# Rev2_7500-8500.net
KiCad netlist of a schematic drawn in Altium Designer
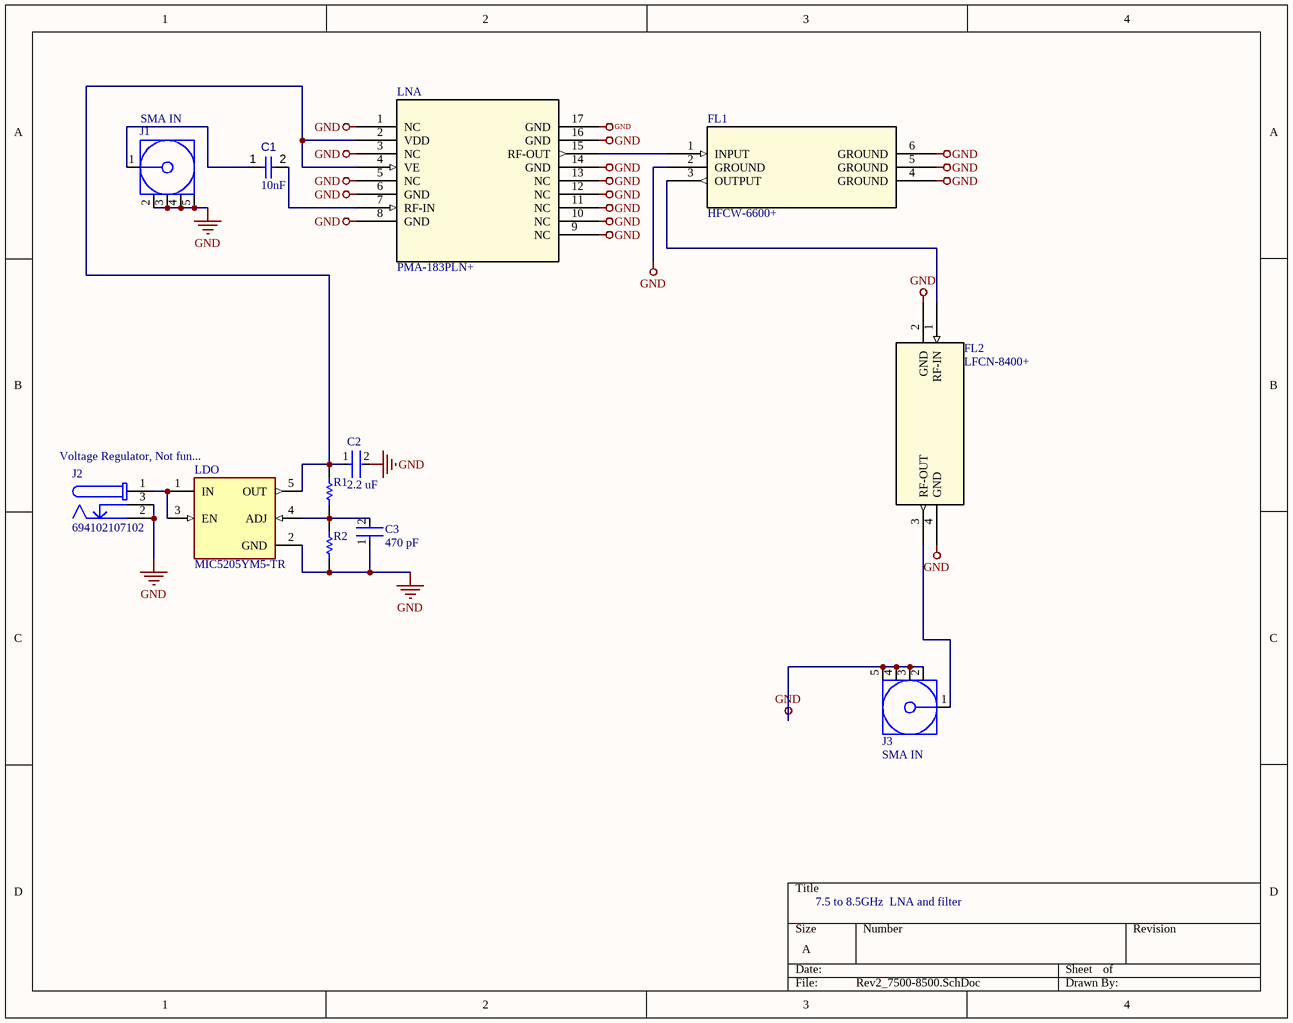
[diagram p0: Rev2_7500-8500.SchDoc]

(export (version "E")
  (design (tool "Eeschema 10.0.6"))
  (components
    (comp (ref "C1")
      (value "10nF")
      (footprint "CAPC0402(1005)60_L")
      (description "Chip Capacitor, 10nF +/-20%, 50V, 0402, Thickness 0.6 mm")
      (fields (field (name "TOLERANCE") "5%") (field (name "Comment") "Capacitor 10nF +/-20% 50V 0402"))
      (libsource (lib "X-Band Circuit") (part "CAP-NP-2"))
    )
    (comp (ref "C2")
      (value "2.2 uF")
      (footprint "FP-GRM188-0_1-e0_2_0_5-MFG")
      (description "Chip Multilayer Ceramic Capacitors for General Purpose, 0603, 2.2uF, X7R, 15%, 10%, 10V")
      (fields (field (name "VOLTAGE") "10V") (field (name "TOLERANCE") "10%"))
      (libsource (lib "Altium Content Vault") (part "11868f565c42a9108669ba33697ecf6"))
    )
    (comp (ref "C3")
      (value "470 pF")
      (footprint "FP-0402-L_1_0_1-W_0_5_0_1-IPC_A")
      (description "General Purpose Ceramic Capacitor, 0402, 470pF, 10%, X7R, 15%, 50V")
      (fields (field (name "TOLERANCE") "10%") (field (name "VOLTAGE") "50V"))
      (libsource (lib "Altium Content Vault") (part "b4654b650e69147ec39a6b967a45e02"))
    )
    (comp (ref "FL1")
      (value "HFCW-6600+")
      (footprint "JC0603C_MNC")
      (description "No Description Available")
      (fields (field (name "COPYRIGHT") "Copyright (C) 2024 Ultra Librarian. All rights reserved."))
      (libsource (lib "HFCW-6600&plus_") (part "HFCW-6600+"))
    )
    (comp (ref "FL2")
      (value "LFCN-8400+")
      (footprint "FV1206-4_MNC")
      (description "No Description Available")
      (fields (field (name "COPYRIGHT") "Copyright (C) 2024 Ultra Librarian. All rights reserved."))
      (libsource (lib "LFCN-8400&plus_") (part "LFCN-8400+"))
    )
    (comp (ref "J1")
      (value "SMA IN")
      (footprint "MOLX-731000114_V")
      (description "SMA Right-Angle PCB Jack Receptacle, Brass Body, Gold Plated, 50 Ohm, 5-Pin THD, RoHS, Tray")
      (fields (field (name "MANUFACTURER") "Molex"))
      (libsource (lib "Altium Content Vault") (part "CN-S-4F-RF5"))
    )
    (comp (ref "J2")
      (value "694102107102")
      (footprint "694102107102")
      (libsource (lib "Altium Content Vault") (part "DC Power Jack"))
    )
    (comp (ref "J3")
      (value "SMA IN")
      (footprint "MOLX-731000114_V")
      (description "SMA Right-Angle PCB Jack Receptacle, Brass Body, Gold Plated, 50 Ohm, 5-Pin THD, RoHS, Tray")
      (fields (field (name "MANUFACTURER") "Molex"))
      (libsource (lib "Altium Content Vault") (part "CN-S-4F-RF5"))
    )
    (comp (ref "LDO")
      (value "MIC5205YM5-TR")
      (footprint "FP-SOT23-5LD-PL-1-MFG")
      (description "IC REG LIN POS ADJ 150MA SOT23-5")
      (fields
        (field (name "MANUFACTURER") "Microchip")
        (field (name "OCTOPART") "https://octopart.com/mic5205ym5-tr-microchip-66802135")
      )
      (libsource (lib "Altium Content Vault") (part "cf2981aadabba2d1f1b05e118016128"))
    )
    (comp (ref "LNA")
      (value "PMA-183PLN+")
      (footprint "JV2579_MNC")
      (description "No Description Available")
      (fields (field (name "COPYRIGHT") "Copyright (C) 2024 Ultra Librarian. All rights reserved."))
      (libsource (lib "PMA-183PLN&plus_") (part "PMA-183PLN+"))
    )
    (comp (ref "R1")
      (value "~")
      (footprint "RESC2013X60X40LL20T25")
      (fields (field (name "MANUFACTURER") "Panasonic") (field (name "PART NUMBER") "ERA6AEB331V"))
      (libsource (lib "Altium Content Vault") (part "RES"))
    )
    (comp (ref "R2")
      (value "~")
      (footprint "RESC1005X40X25ML10T10")
      (fields (field (name "PART NUMBER") "ERA-2AEB621X") (field (name "MANUFACTURER") "Panasonic"))
      (libsource (lib "Altium Content Vault") (part "RES"))
    )
  )
  (nets
    (net (code "1") (name "GND") (class "Default")
      (node (ref "C2") (pin "2") (pinfunction "2_2") (pintype "passive"))
      (node (ref "C3") (pin "1") (pinfunction "1_1") (pintype "passive"))
      (node (ref "FL1") (pin "2") (pinfunction "GROUND_2") (pintype "power_in"))
      (node (ref "FL1") (pin "4") (pinfunction "GROUND_4") (pintype "power_in"))
      (node (ref "FL1") (pin "5") (pinfunction "GROUND_5") (pintype "power_in"))
      (node (ref "FL1") (pin "6") (pinfunction "GROUND_6") (pintype "power_in"))
      (node (ref "FL2") (pin "2") (pinfunction "GND_2") (pintype "power_in"))
      (node (ref "FL2") (pin "4") (pinfunction "GND_4") (pintype "power_in"))
      (node (ref "J1") (pin "2") (pinfunction "2_2") (pintype "passive"))
      (node (ref "J1") (pin "3") (pinfunction "3_3") (pintype "passive"))
      (node (ref "J1") (pin "4") (pinfunction "4_4") (pintype "passive"))
      (node (ref "J1") (pin "5") (pinfunction "5_5") (pintype "passive"))
      (node (ref "J2") (pin "2") (pinfunction "2_2") (pintype "passive"))
      (node (ref "J2") (pin "3") (pinfunction "3_3") (pintype "passive"))
      (node (ref "J3") (pin "2") (pinfunction "2_2") (pintype "passive"))
      (node (ref "J3") (pin "3") (pinfunction "3_3") (pintype "passive"))
      (node (ref "J3") (pin "4") (pinfunction "4_4") (pintype "passive"))
      (node (ref "J3") (pin "5") (pinfunction "5_5") (pintype "passive"))
      (node (ref "LDO") (pin "2") (pinfunction "GND_2") (pintype "power_in"))
      (node (ref "LNA") (pin "1") (pinfunction "NC_1") (pintype "passive"))
      (node (ref "LNA") (pin "10") (pinfunction "NC_10") (pintype "passive"))
      (node (ref "LNA") (pin "11") (pinfunction "NC_11") (pintype "passive"))
      (node (ref "LNA") (pin "12") (pinfunction "NC_12") (pintype "passive"))
      (node (ref "LNA") (pin "13") (pinfunction "NC_13") (pintype "passive"))
      (node (ref "LNA") (pin "14") (pinfunction "GND_14") (pintype "power_in"))
      (node (ref "LNA") (pin "16") (pinfunction "GND_16") (pintype "power_in"))
      (node (ref "LNA") (pin "17") (pinfunction "GND_17") (pintype "power_in"))
      (node (ref "LNA") (pin "3") (pinfunction "NC_3") (pintype "passive"))
      (node (ref "LNA") (pin "5") (pinfunction "NC_5") (pintype "passive"))
      (node (ref "LNA") (pin "6") (pinfunction "GND_6") (pintype "power_in"))
      (node (ref "LNA") (pin "8") (pinfunction "GND_8") (pintype "power_in"))
      (node (ref "LNA") (pin "9") (pinfunction "NC_9") (pintype "passive"))
      (node (ref "R2") (pin "2") (pinfunction "2_2") (pintype "passive"))
    )
    (net (code "2") (name "Net-(C1-Pad1)") (class "Default")
      (node (ref "C1") (pin "1") (pinfunction "1_1") (pintype "passive"))
      (node (ref "J1") (pin "1") (pinfunction "1_1") (pintype "passive"))
    )
    (net (code "3") (name "Net-(FL1-INPUT)") (class "Default")
      (node (ref "FL1") (pin "1") (pinfunction "INPUT_1") (pintype "input"))
      (node (ref "LNA") (pin "15") (pinfunction "RF-OUT_15") (pintype "output"))
    )
    (net (code "4") (name "Net-(FL1-OUTPUT)") (class "Default")
      (node (ref "FL1") (pin "3") (pinfunction "OUTPUT_3") (pintype "output"))
      (node (ref "FL2") (pin "1") (pinfunction "RF-IN_1") (pintype "input"))
    )
    (net (code "5") (name "Net-(FL2-RF-OUT)") (class "Default")
      (node (ref "FL2") (pin "3") (pinfunction "RF-OUT_3") (pintype "output"))
      (node (ref "J3") (pin "1") (pinfunction "1_1") (pintype "passive"))
    )
    (net (code "6") (name "Net-(LDO-ADJ)") (class "Default")
      (node (ref "C3") (pin "2") (pinfunction "2_2") (pintype "passive"))
      (node (ref "LDO") (pin "4") (pinfunction "ADJ_4") (pintype "input"))
      (node (ref "R1") (pin "2") (pinfunction "2_2") (pintype "passive"))
      (node (ref "R2") (pin "1") (pinfunction "1_1") (pintype "passive"))
    )
    (net (code "7") (name "Net-(LDO-EN)") (class "Default")
      (node (ref "J2") (pin "1") (pinfunction "1_1") (pintype "passive"))
      (node (ref "LDO") (pin "1") (pinfunction "IN_1") (pintype "power_in"))
      (node (ref "LDO") (pin "3") (pinfunction "EN_3") (pintype "input"))
    )
    (net (code "8") (name "Net-(LDO-OUT)") (class "Default")
      (node (ref "C2") (pin "1") (pinfunction "1_1") (pintype "passive"))
      (node (ref "LDO") (pin "5") (pinfunction "OUT_5") (pintype "output"))
      (node (ref "LNA") (pin "2") (pinfunction "VDD_2") (pintype "power_in"))
      (node (ref "LNA") (pin "4") (pinfunction "VE_4") (pintype "input"))
      (node (ref "R1") (pin "1") (pinfunction "1_1") (pintype "passive"))
    )
    (net (code "9") (name "Net-(LNA-RF-IN)") (class "Default")
      (node (ref "C1") (pin "2") (pinfunction "2_2") (pintype "passive"))
      (node (ref "LNA") (pin "7") (pinfunction "RF-IN_7") (pintype "input"))
    )
  )
)
